# Microcontroller.net
KiCad netlist of a schematic drawn in Altium Designer
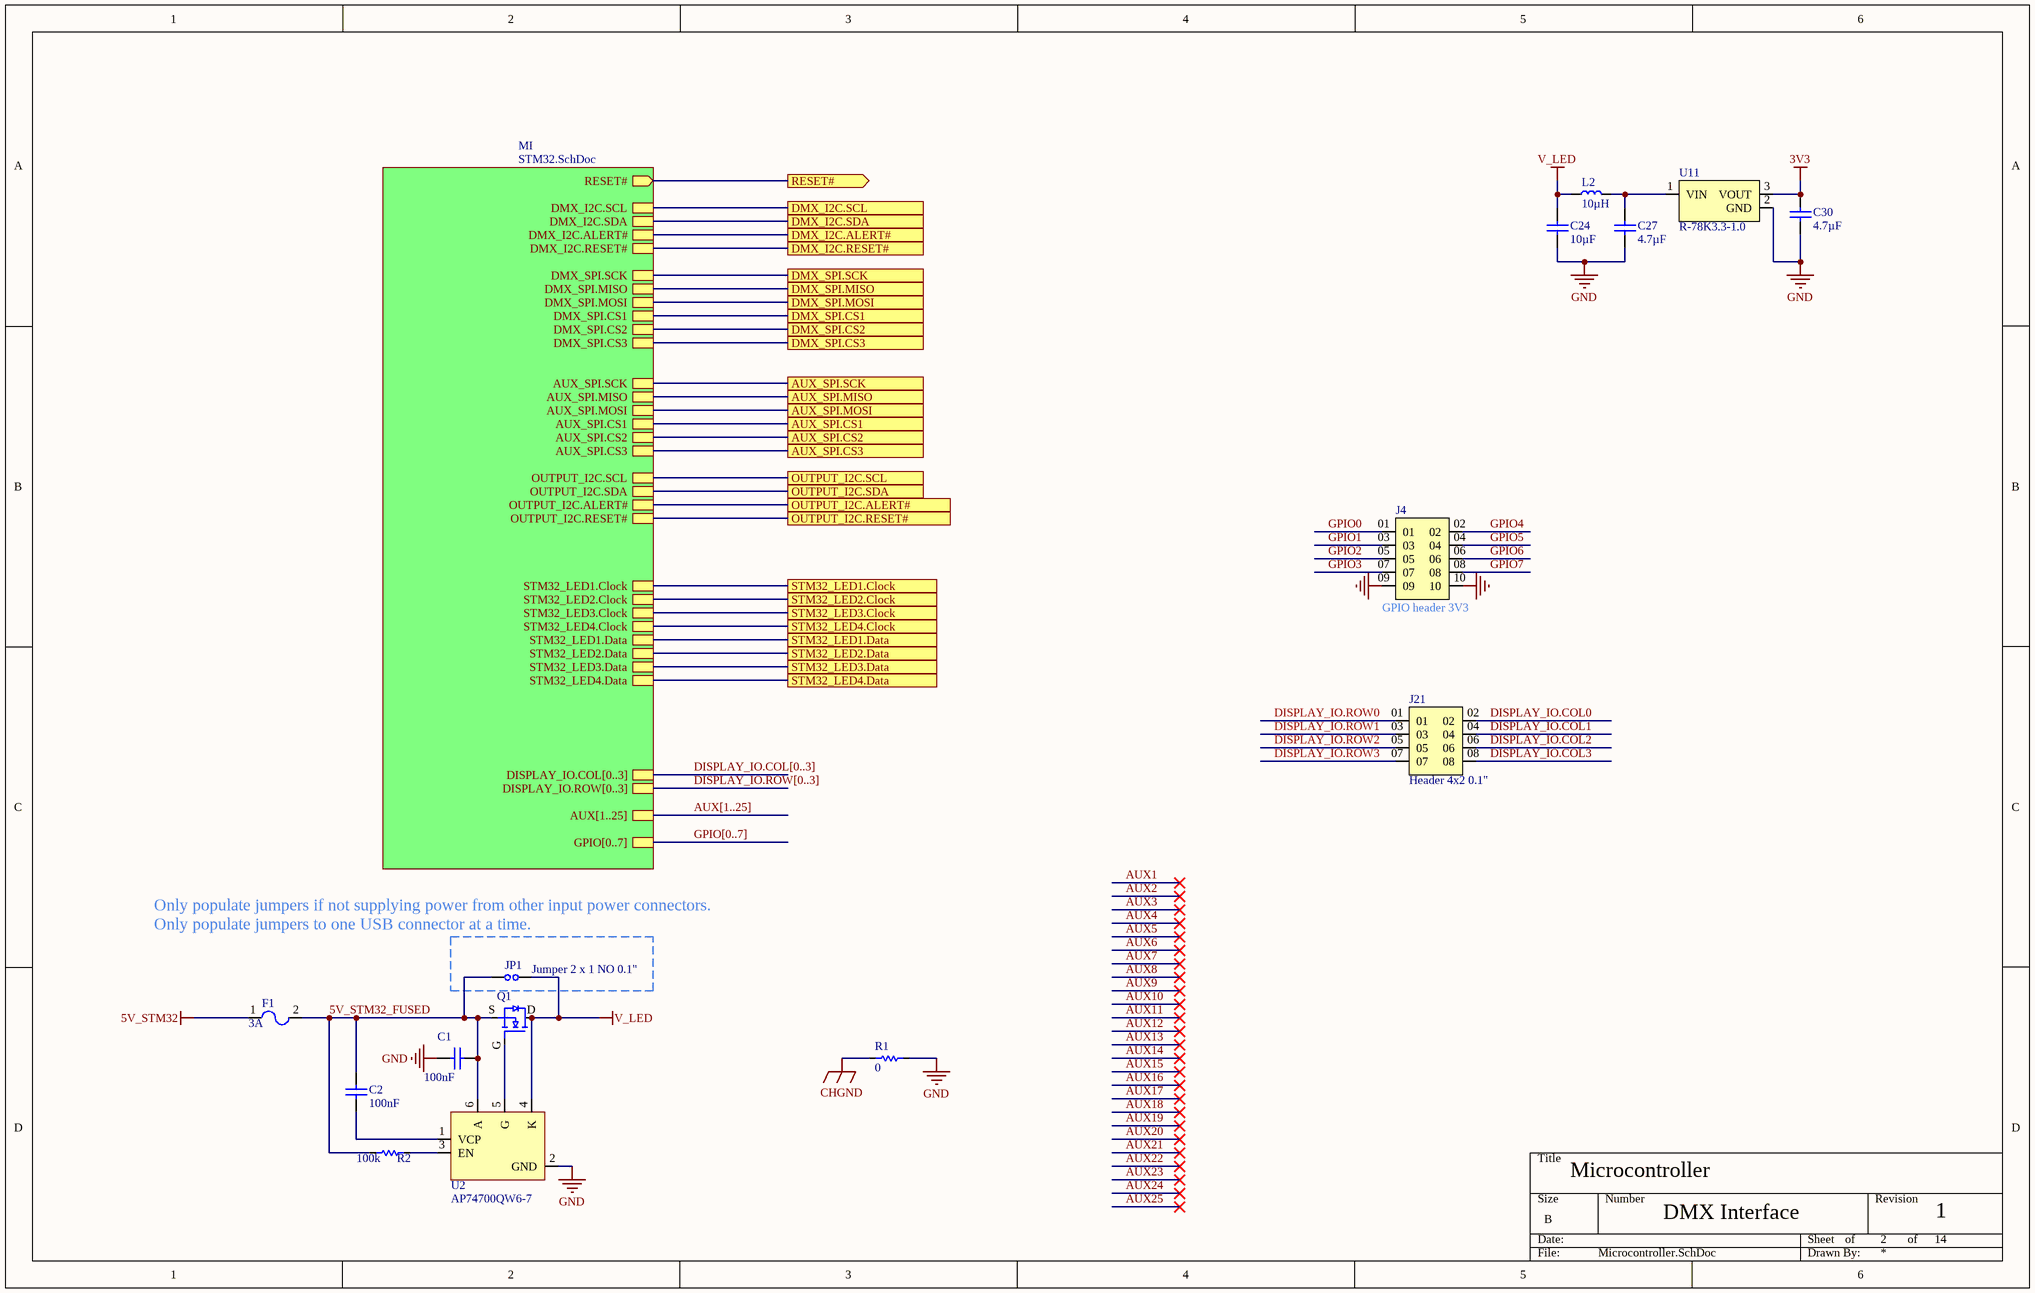
[diagram p0: Microcontroller.SchDoc]

(export (version "E")
  (design (tool "Eeschema 10.0.6"))
  (components
    (comp (ref "C1")
      (value "100nF")
      (footprint "CAPC1608X10N_0603_MED")
      (fields (field (name "Comment") "CC0603KRX7R0BB104"))
      (libsource (lib "Equus Computer Systems") (part "CAP-NP-2"))
    )
    (comp (ref "C2")
      (value "100nF")
      (footprint "CAPC1608X10N_0603_MED")
      (fields (field (name "Comment") "CC0603KRX7R0BB104"))
      (libsource (lib "Equus Computer Systems") (part "CAP-NP-2"))
    )
    (comp (ref "C24")
      (value "10µF")
      (footprint "CAPC2012X14N_0805_MED")
      (description "Ceramic Capacitor, Multilayer, Ceramic, 10uF, 50V, 10%, X6S, 0805")
      (fields (field (name "TOLERANCE") "10%") (field (name "Comment") "GRM21BR61H106KE43L"))
      (libsource (lib "Equus Computer Systems") (part "CAP-NP-2"))
    )
    (comp (ref "C27")
      (value "4.7µF")
      (footprint "CAPC2012X14N_0805_MED")
      (fields (field (name "TOLERANCE") "10%") (field (name "Comment") "GRM21BR61H475KE51L"))
      (libsource (lib "Equus Computer Systems") (part "CAP-NP-2"))
    )
    (comp (ref "C30")
      (value "4.7µF")
      (footprint "CAPC2012X14N_0805_MED")
      (fields (field (name "TOLERANCE") "10%") (field (name "Comment") "GRM21BR61H475KE51L"))
      (libsource (lib "Equus Computer Systems") (part "CAP-NP-2"))
    )
    (comp (ref "F1")
      (value "0ZCG0300FF2B")
      (footprint "FUSE4532X1.55N_1812MED")
      (description "PTC Resettable Fuse, 6V, 3A Surface Mount")
      (fields (field (name "CURRENT RATING") "3A"))
      (libsource (lib "Equus Computer Systems") (part "Fuse"))
    )
    (comp (ref "J4")
      (value "Header 5x2 0.1\"")
      (footprint "HEADER 5x2 0.1 Through hole")
      (description "Board Connector Tall, 10 Contact(s), 2 Row(s), Male, Straight, 0.1 inch Pitch")
      (libsource (lib "Equus Computer Systems") (part "Header 5x2 0.1{dblquote}"))
    )
    (comp (ref "J21")
      (value "Header 4x2 0.1\"")
      (footprint "Header 4x2 0.1\"")
      (description "Board Connector, 8 Contact(s), 2 Row(s), Female, 0.1 inch Pitch")
      (libsource (lib "Equus Computer Systems") (part "Header 4x2"))
    )
    (comp (ref "JP1")
      (value "Jumper 2 x 1 NO 0.1\"")
      (footprint "FP-M20-9990245-MFG")
      (libsource (lib "Equus Computer Systems") (part "Jumper 2 NO"))
    )
    (comp (ref "L2")
      (value "10µH")
      (footprint "FP-SRN5040-MFG")
      (description "General Purpose Inductor, 10uH, 20%, 1 Element, Ferrite-Core, SMD, 2020")
      (fields (field (name "TOLERANCE") "20%") (field (name "Comment") "SRN5040-100M"))
      (libsource (lib "Equus Computer Systems") (part "IND-2"))
    )
    (comp (ref "Q1")
      (value "BUK9880-55A/CUX")
      (footprint "SOT230P700X180-4N")
      (description "BUK9880 Series 55 V 7A 73 mOhm N-Channel TrenchMOS Logic Level FET - SC-73")
      (libsource (lib "Equus Computer Systems") (part "TRANS-MOSFET"))
    )
    (comp (ref "R1")
      (value "0")
      (footprint "RESC1608X06N_0603_MED")
      (description "RC Series 0603 0.1 W 0 Ohm Jumper Surface Mount Thick Film Chip Resistor")
      (fields (field (name "TOLERANCE") "1%") (field (name "POWER") "100mW"))
      (libsource (lib "Equus Computer Systems") (part "RES-2"))
    )
    (comp (ref "R2")
      (value "100k")
      (footprint "RESC1608X06N_0603_MED")
      (fields
        (field (name "POWER") "100mW")
        (field (name "TOLERANCE") "0.5%")
        (field (name "Comment") "RC0603DR-07100KL")
      )
      (libsource (lib "Equus Computer Systems") (part "RES-2"))
    )
    (comp (ref "U2")
      (value "AP74700QW6-7")
      (footprint "SOT95P285X130-6N")
      (description "ORController N-Channel Single Automotive AEC-Q100 6-Pin SOT-26 T/R")
      (libsource (lib "Equus Computer Systems") (part "AP74700QW6-7-Symbol-1"))
    )
    (comp (ref "U11")
      (value "R-78K3.3-1.0")
      (footprint "R-78K3.3-1.0-Footprint-1")
      (description "R-78K-1.0 Series Single Output 3.3 V 1 A Non Isolated DC/DC Converter - SIP-3")
      (libsource (lib "Equus Computer Systems") (part "R-78K3.3-1.0-Symbol-1"))
    )
  )
  (nets
    (net (code "1") (name "/5V_STM32_FUSED") (class "Default")
      (node (ref "C1") (pin "1") (pinfunction "1_1") (pintype "passive"))
      (node (ref "C2") (pin "2") (pinfunction "2_2") (pintype "passive"))
      (node (ref "F1") (pin "2") (pinfunction "2_2") (pintype "passive"))
      (node (ref "JP1") (pin "1") (pinfunction "1_1") (pintype "passive"))
      (node (ref "Q1") (pin "S") (pinfunction "S_S") (pintype "passive"))
      (node (ref "R2") (pin "1") (pinfunction "1_1") (pintype "passive"))
      (node (ref "U2") (pin "6") (pinfunction "A_6") (pintype "passive"))
    )
    (net (code "34") (name "/DISPLAY_IO.COL0") (class "Default")
      (node (ref "J21") (pin "02") (pinfunction "02_02") (pintype "passive"))
    )
    (net (code "35") (name "/DISPLAY_IO.COL1") (class "Default")
      (node (ref "J21") (pin "04") (pinfunction "04_04") (pintype "passive"))
    )
    (net (code "36") (name "/DISPLAY_IO.COL2") (class "Default")
      (node (ref "J21") (pin "06") (pinfunction "06_06") (pintype "passive"))
    )
    (net (code "37") (name "/DISPLAY_IO.COL3") (class "Default")
      (node (ref "J21") (pin "08") (pinfunction "08_08") (pintype "passive"))
    )
    (net (code "39") (name "/DISPLAY_IO.ROW0") (class "Default")
      (node (ref "J21") (pin "01") (pinfunction "01_01") (pintype "passive"))
    )
    (net (code "40") (name "/DISPLAY_IO.ROW1") (class "Default")
      (node (ref "J21") (pin "03") (pinfunction "03_03") (pintype "passive"))
    )
    (net (code "41") (name "/DISPLAY_IO.ROW2") (class "Default")
      (node (ref "J21") (pin "05") (pinfunction "05_05") (pintype "passive"))
    )
    (net (code "42") (name "/DISPLAY_IO.ROW3") (class "Default")
      (node (ref "J21") (pin "07") (pinfunction "07_07") (pintype "passive"))
    )
    (net (code "54") (name "/GPIO0") (class "Default")
      (node (ref "J4") (pin "01") (pinfunction "01_01") (pintype "passive"))
    )
    (net (code "55") (name "/GPIO1") (class "Default")
      (node (ref "J4") (pin "03") (pinfunction "03_03") (pintype "passive"))
    )
    (net (code "56") (name "/GPIO2") (class "Default")
      (node (ref "J4") (pin "05") (pinfunction "05_05") (pintype "passive"))
    )
    (net (code "57") (name "/GPIO3") (class "Default")
      (node (ref "J4") (pin "07") (pinfunction "07_07") (pintype "passive"))
    )
    (net (code "58") (name "/GPIO4") (class "Default")
      (node (ref "J4") (pin "02") (pinfunction "02_02") (pintype "passive"))
    )
    (net (code "59") (name "/GPIO5") (class "Default")
      (node (ref "J4") (pin "04") (pinfunction "04_04") (pintype "passive"))
    )
    (net (code "60") (name "/GPIO6") (class "Default")
      (node (ref "J4") (pin "06") (pinfunction "06_06") (pintype "passive"))
    )
    (net (code "61") (name "/GPIO7") (class "Default")
      (node (ref "J4") (pin "08") (pinfunction "08_08") (pintype "passive"))
    )
    (net (code "76") (name "3V3") (class "Default")
      (node (ref "C30") (pin "2") (pinfunction "2_2") (pintype "passive"))
      (node (ref "U11") (pin "3") (pinfunction "VOUT_3") (pintype "passive"))
    )
    (net (code "77") (name "5V_STM32") (class "Default")
      (node (ref "F1") (pin "1") (pinfunction "1_1") (pintype "passive"))
    )
    (net (code "78") (name "CHGND") (class "Default")
      (node (ref "R1") (pin "1") (pinfunction "1_1") (pintype "passive"))
    )
    (net (code "79") (name "GND") (class "Default")
      (node (ref "C1") (pin "2") (pinfunction "2_2") (pintype "passive"))
      (node (ref "C24") (pin "1") (pinfunction "1_1") (pintype "passive"))
      (node (ref "C27") (pin "1") (pinfunction "1_1") (pintype "passive"))
      (node (ref "C30") (pin "1") (pinfunction "1_1") (pintype "passive"))
      (node (ref "J4") (pin "09") (pinfunction "09_09") (pintype "passive"))
      (node (ref "J4") (pin "10") (pinfunction "10_10") (pintype "passive"))
      (node (ref "R1") (pin "2") (pinfunction "2_2") (pintype "passive"))
      (node (ref "U11") (pin "2") (pinfunction "GND_2") (pintype "power_in"))
      (node (ref "U2") (pin "2") (pinfunction "GND_2") (pintype "passive"))
    )
    (net (code "80") (name "Net-(U2-EN)") (class "Default")
      (node (ref "R2") (pin "2") (pinfunction "2_2") (pintype "passive"))
      (node (ref "U2") (pin "3") (pinfunction "EN_3") (pintype "passive"))
    )
    (net (code "81") (name "Net-(U2-G)") (class "Default")
      (node (ref "Q1") (pin "G") (pinfunction "G_G") (pintype "passive"))
      (node (ref "U2") (pin "5") (pinfunction "G_5") (pintype "passive"))
    )
    (net (code "82") (name "Net-(U2-VCP)") (class "Default")
      (node (ref "C2") (pin "1") (pinfunction "1_1") (pintype "passive"))
      (node (ref "U2") (pin "1") (pinfunction "VCP_1") (pintype "passive"))
    )
    (net (code "83") (name "Net-(U11-VIN)") (class "Default")
      (node (ref "C27") (pin "2") (pinfunction "2_2") (pintype "passive"))
      (node (ref "L2") (pin "2") (pinfunction "2_2") (pintype "passive"))
      (node (ref "U11") (pin "1") (pinfunction "VIN_1") (pintype "passive"))
    )
    (net (code "84") (name "V_LED") (class "Default")
      (node (ref "C24") (pin "2") (pinfunction "2_2") (pintype "passive"))
      (node (ref "JP1") (pin "2") (pinfunction "2_2") (pintype "passive"))
      (node (ref "L2") (pin "1") (pinfunction "1_1") (pintype "passive"))
      (node (ref "Q1") (pin "D") (pinfunction "D_D") (pintype "passive"))
      (node (ref "U2") (pin "4") (pinfunction "K_4") (pintype "passive"))
    )
  )
)
